# Chanel.net
KiCad netlist of a schematic drawn in Altium Designer
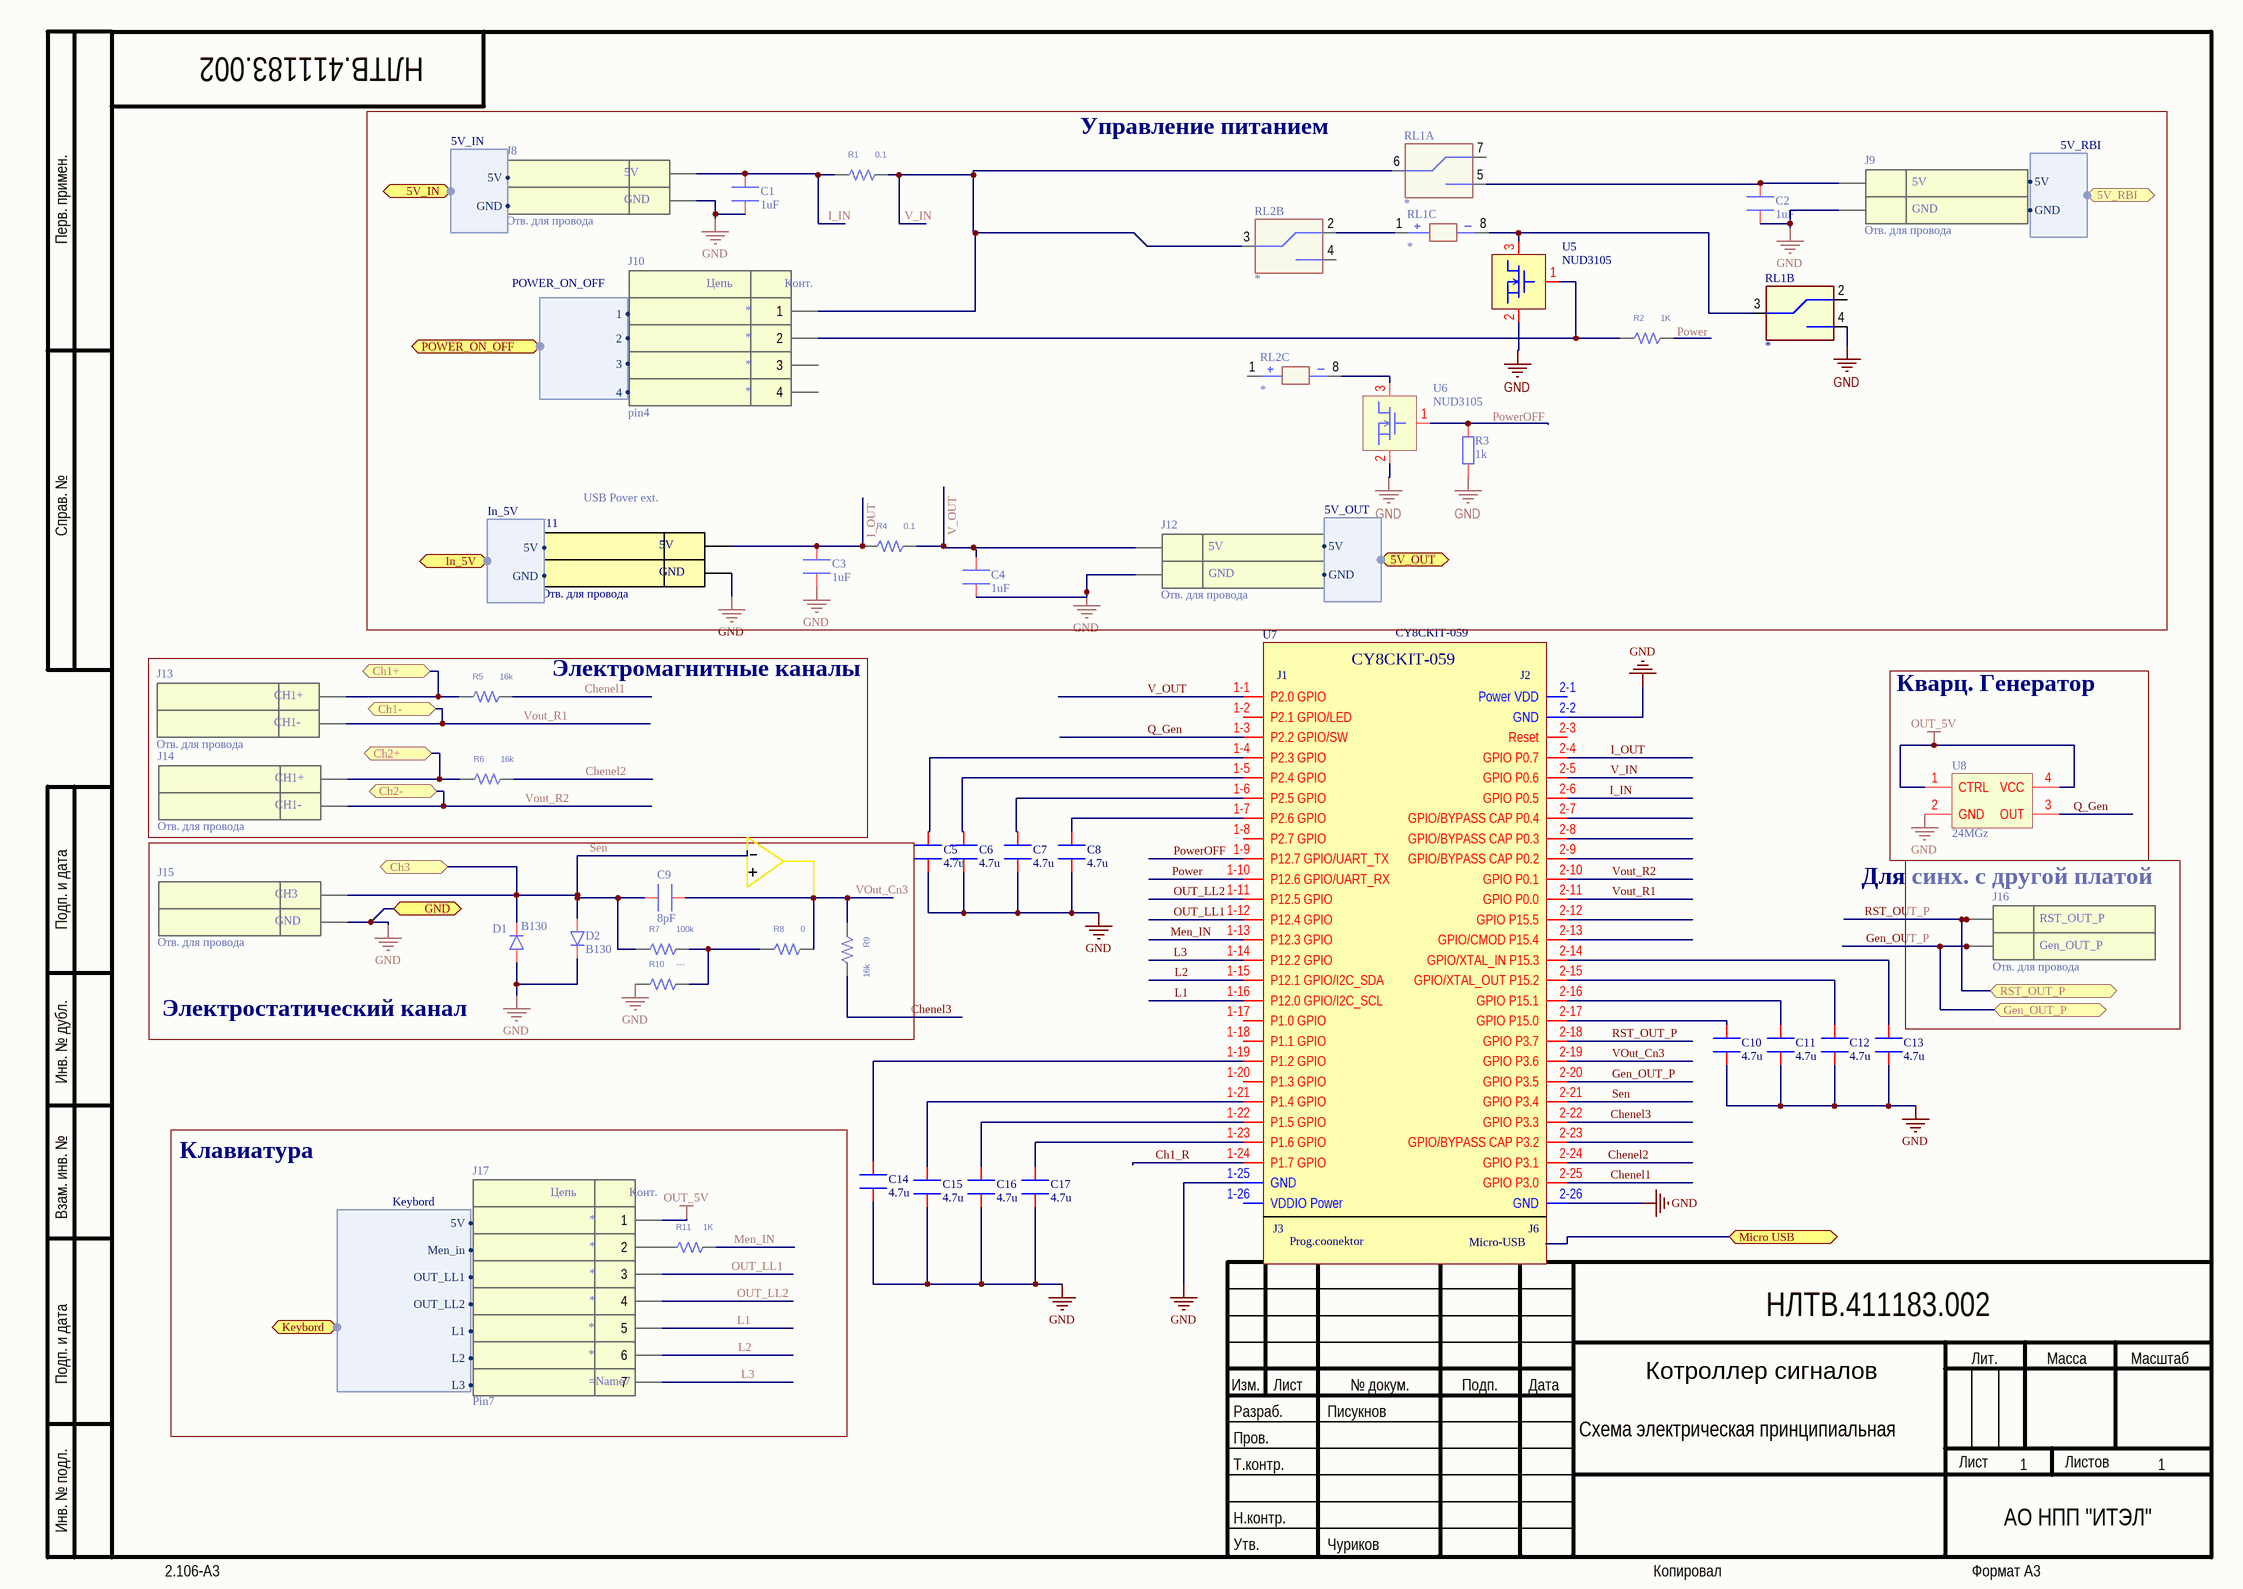
[diagram p0: Chanel.SchDoc]

(export (version "E")
  (design (tool "Eeschema 10.0.6"))
  (components
    (comp (ref "C1") (value "1uF") (footprint "SMD0603") (libsource (lib "Lib_001") (part "CAP")))
    (comp (ref "C2") (value "1uF") (footprint "SMD0603") (libsource (lib "Lib_001") (part "CAP")))
    (comp (ref "C3") (value "1uF") (footprint "SMD0603") (libsource (lib "Lib_001") (part "CAP")))
    (comp (ref "C4") (value "1uF") (footprint "SMD0603") (libsource (lib "Lib_001") (part "CAP")))
    (comp (ref "C5") (value "4.7u") (footprint "SMD0805") (libsource (lib "Lib_001") (part "CAP")))
    (comp (ref "C6") (value "4.7u") (footprint "SMD0805") (libsource (lib "Lib_001") (part "CAP")))
    (comp (ref "C7") (value "4.7u") (footprint "SMD0805") (libsource (lib "Lib_001") (part "CAP")))
    (comp (ref "C8") (value "4.7u") (footprint "SMD0805") (libsource (lib "Lib_001") (part "CAP")))
    (comp (ref "C9") (value "8pF") (footprint "SMD0805") (libsource (lib "Lib_001") (part "CAP")))
    (comp (ref "C10") (value "4.7u") (footprint "SMD0805") (libsource (lib "Lib_001") (part "CAP")))
    (comp (ref "C11") (value "4.7u") (footprint "SMD0805") (libsource (lib "Lib_001") (part "CAP")))
    (comp (ref "C12") (value "4.7u") (footprint "SMD0805") (libsource (lib "Lib_001") (part "CAP")))
    (comp (ref "C13") (value "4.7u") (footprint "SMD0805") (libsource (lib "Lib_001") (part "CAP")))
    (comp (ref "C14") (value "4.7u") (footprint "SMD0805") (libsource (lib "Lib_001") (part "CAP")))
    (comp (ref "C15") (value "4.7u") (footprint "SMD0805") (libsource (lib "Lib_001") (part "CAP")))
    (comp (ref "C16") (value "4.7u") (footprint "SMD0805") (libsource (lib "Lib_001") (part "CAP")))
    (comp (ref "C17") (value "4.7u") (footprint "SMD0805") (libsource (lib "Lib_001") (part "CAP")))
    (comp (ref "D1") (value "B130") (footprint "SMA DIOD") (libsource (lib "Lib_001") (part "DIOD")))
    (comp (ref "D2") (value "B130") (footprint "SMA DIOD") (libsource (lib "Lib_001") (part "DIOD")))
    (comp (ref "J8")
      (value "Отв. для провода")
      (footprint "JAMPER 2")
      (libsource (lib "") (part "pin2_continuation_1"))
    )
    (comp (ref "J9")
      (value "Отв. для провода")
      (footprint "JAMPER 2")
      (libsource (lib "Lib_001") (part "pin2_continuation"))
    )
    (comp (ref "J10") (value "pin4") (footprint "MF-4MA") (libsource (lib "Lib_001") (part "pin4")))
    (comp (ref "J11")
      (value "Отв. для провода")
      (footprint "JAMPER 2")
      (libsource (lib "") (part "pin2_continuation_1"))
    )
    (comp (ref "J12")
      (value "Отв. для провода")
      (footprint "JAMPER 2")
      (libsource (lib "Lib_001") (part "pin2_continuation"))
    )
    (comp (ref "J13")
      (value "Отв. для провода")
      (footprint "JAMPER 2")
      (libsource (lib "") (part "pin2_continuation_1"))
    )
    (comp (ref "J14")
      (value "Отв. для провода")
      (footprint "JAMPER 2")
      (libsource (lib "") (part "pin2_continuation_1"))
    )
    (comp (ref "J15")
      (value "Отв. для провода")
      (footprint "JAMPER 2")
      (libsource (lib "") (part "pin2_continuation_1"))
    )
    (comp (ref "J16")
      (value "Отв. для провода")
      (footprint "JAMPER 2")
      (libsource (lib "Lib_001") (part "pin2_continuation"))
    )
    (comp (ref "J17") (value "Pin7") (footprint "ECH350V-06P") (libsource (lib "Lib_001") (part "Pin7")))
    (comp (ref "R1")
      (value "0.1")
      (footprint "SMD1206")
      (fields (field (name "POWER") "RMAX") (field (name "VOLTAGE") "RVMAX"))
      (libsource (lib "*") (part "R"))
    )
    (comp (ref "R2")
      (value "1K")
      (footprint "SMD1206")
      (fields (field (name "POWER") "RMAX") (field (name "VOLTAGE") "RVMAX"))
      (libsource (lib "*") (part "R"))
    )
    (comp (ref "R3") (value "1k") (footprint "SMD0805") (libsource (lib "Lib_001") (part "RES_SMD")))
    (comp (ref "R4")
      (value "0.1")
      (footprint "SMD1206")
      (fields (field (name "POWER") "RMAX") (field (name "VOLTAGE") "RVMAX"))
      (libsource (lib "*") (part "R"))
    )
    (comp (ref "R5")
      (value "16k")
      (footprint "SMD1206")
      (fields (field (name "POWER") "RMAX") (field (name "VOLTAGE") "RVMAX"))
      (libsource (lib "*") (part "R"))
    )
    (comp (ref "R6")
      (value "16k")
      (footprint "SMD1206")
      (fields (field (name "POWER") "RMAX") (field (name "VOLTAGE") "RVMAX"))
      (libsource (lib "*") (part "R"))
    )
    (comp (ref "R7")
      (value "100k")
      (footprint "SMD1206")
      (fields (field (name "POWER") "RMAX") (field (name "VOLTAGE") "RVMAX"))
      (libsource (lib "*") (part "R"))
    )
    (comp (ref "R8")
      (value "0")
      (footprint "SMD1206")
      (fields (field (name "POWER") "RMAX") (field (name "VOLTAGE") "RVMAX"))
      (libsource (lib "*") (part "R"))
    )
    (comp (ref "R9")
      (value "16k")
      (footprint "SMD1206")
      (fields (field (name "POWER") "RMAX") (field (name "VOLTAGE") "RVMAX"))
      (libsource (lib "*") (part "R"))
    )
    (comp (ref "R10")
      (value "---")
      (footprint "SMD1206")
      (fields (field (name "POWER") "RMAX") (field (name "VOLTAGE") "RVMAX"))
      (libsource (lib "*") (part "R"))
    )
    (comp (ref "R11")
      (value "1K")
      (footprint "SMD1206")
      (fields (field (name "POWER") "RMAX") (field (name "VOLTAGE") "RVMAX"))
      (libsource (lib "*") (part "R"))
    )
    (comp (ref "RL1") (value "*") (footprint "IM06GR") (libsource (lib "Lib_001") (part "Relay_2 switch")))
    (comp (ref "RL2") (value "*") (footprint "IM06GR") (libsource (lib "Lib_001") (part "Relay_2 switch")))
    (comp (ref "U5") (value "NUD3105") (footprint "SOT-23") (libsource (lib "Lib_001") (part "NUD3105")))
    (comp (ref "U6") (value "NUD3105") (footprint "SOT-23") (libsource (lib "Lib_001") (part "NUD3105")))
    (comp (ref "U7")
      (value "CY8CKIT-059")
      (footprint "CY8CKIT-059")
      (libsource (lib "Lib_001") (part "CY8CKIT-059"))
    )
    (comp (ref "U8") (value "24MGz") (libsource (lib "Lib_001") (part "KXO-97")))
  )
  (nets
    (net (code "7") (name "/Ch1+") (class "Default")
      (node (ref "J13") (pin "1") (pinfunction "1_1") (pintype "passive"))
      (node (ref "R5") (pin "1") (pinfunction "1_1") (pintype "passive"))
    )
    (net (code "8") (name "/Ch1_R") (class "Default")
      (node (ref "U7") (pin "1-24") (pinfunction "P1.7_GPIO_1-24") (pintype "passive"))
    )
    (net (code "9") (name "/Ch2+") (class "Default")
      (node (ref "J14") (pin "1") (pinfunction "1_1") (pintype "passive"))
      (node (ref "R6") (pin "1") (pinfunction "1_1") (pintype "passive"))
    )
    (net (code "10") (name "/Chenel1") (class "Default")
      (node (ref "R5") (pin "2") (pinfunction "2_2") (pintype "passive"))
      (node (ref "U7") (pin "2-25") (pinfunction "GPIO_P3.0_2-25") (pintype "passive"))
    )
    (net (code "11") (name "/Chenel2") (class "Default")
      (node (ref "R6") (pin "2") (pinfunction "2_2") (pintype "passive"))
      (node (ref "U7") (pin "2-24") (pinfunction "GPIO_P3.1_2-24") (pintype "passive"))
    )
    (net (code "12") (name "/Chenel3") (class "Default")
      (node (ref "R9") (pin "2") (pinfunction "2_2") (pintype "passive"))
      (node (ref "U7") (pin "2-22") (pinfunction "GPIO_P3.3_2-22") (pintype "passive"))
    )
    (net (code "13") (name "/Gen_OUT_P") (class "Default")
      (node (ref "J16") (pin "2") (pinfunction "2_2") (pintype "passive"))
      (node (ref "U7") (pin "2-20") (pinfunction "GPIO_P3.5_2-20") (pintype "passive"))
    )
    (net (code "14") (name "/I_IN") (class "Default")
      (node (ref "C1") (pin "2") (pinfunction "2_2") (pintype "passive"))
      (node (ref "J8") (pin "1") (pinfunction "1_1") (pintype "passive"))
      (node (ref "R1") (pin "1") (pinfunction "1_1") (pintype "passive"))
      (node (ref "U7") (pin "2-6") (pinfunction "GPIO_P0.5_2-6") (pintype "passive"))
    )
    (net (code "15") (name "/I_OUT") (class "Default")
      (node (ref "C3") (pin "2") (pinfunction "2_2") (pintype "passive"))
      (node (ref "J11") (pin "1") (pinfunction "1_1") (pintype "passive"))
      (node (ref "R4") (pin "1") (pinfunction "1_1") (pintype "passive"))
      (node (ref "U7") (pin "2-4") (pinfunction "GPIO_P0.7_2-4") (pintype "passive"))
    )
    (net (code "16") (name "/L1") (class "Default")
      (node (ref "J17") (pin "5") (pinfunction "5_5") (pintype "passive"))
      (node (ref "U7") (pin "1-16") (pinfunction "P12.0_GPIO/I2C_SCL_1-16") (pintype "passive"))
    )
    (net (code "17") (name "/L2") (class "Default")
      (node (ref "J17") (pin "6") (pinfunction "6_6") (pintype "passive"))
      (node (ref "U7") (pin "1-15") (pinfunction "P12.1_GPIO/I2C_SDA_1-15") (pintype "passive"))
    )
    (net (code "18") (name "/L3") (class "Default")
      (node (ref "J17") (pin "7") (pinfunction "7_7") (pintype "passive"))
      (node (ref "U7") (pin "1-14") (pinfunction "P12.2_GPIO_1-14") (pintype "passive"))
    )
    (net (code "19") (name "/Men_IN") (class "Default")
      (node (ref "R11") (pin "2") (pinfunction "2_2") (pintype "passive"))
      (node (ref "U7") (pin "1-13") (pinfunction "P12.3_GPIO_1-13") (pintype "passive"))
    )
    (net (code "21") (name "/OUT_LL1") (class "Default")
      (node (ref "J17") (pin "3") (pinfunction "3_3") (pintype "passive"))
      (node (ref "U7") (pin "1-12") (pinfunction "P12.4_GPIO_1-12") (pintype "passive"))
    )
    (net (code "22") (name "/OUT_LL2") (class "Default")
      (node (ref "J17") (pin "4") (pinfunction "4_4") (pintype "passive"))
      (node (ref "U7") (pin "1-11") (pinfunction "P12.5_GPIO_1-11") (pintype "passive"))
    )
    (net (code "23") (name "/Power") (class "Default")
      (node (ref "U7") (pin "1-10") (pinfunction "P12.6_GPIO/UART_RX_1-10") (pintype "passive"))
    )
    (net (code "24") (name "/PowerOFF") (class "Default")
      (node (ref "U7") (pin "1-9") (pinfunction "P12.7_GPIO/UART_TX_1-9") (pintype "passive"))
    )
    (net (code "25") (name "/Q_Gen") (class "Default")
      (node (ref "U7") (pin "1-3") (pinfunction "P2.2_GPIO/SW_1-3") (pintype "passive"))
      (node (ref "U8") (pin "3") (pinfunction "OUT_3") (pintype "passive"))
    )
    (net (code "26") (name "/RST_OUT_P") (class "Default")
      (node (ref "J16") (pin "1") (pinfunction "1_1") (pintype "passive"))
      (node (ref "U7") (pin "2-18") (pinfunction "GPIO_P3.7_2-18") (pintype "passive"))
    )
    (net (code "27") (name "/Sen") (class "Default")
      (node (ref "C9") (pin "2") (pinfunction "2_2") (pintype "passive"))
      (node (ref "D1") (pin "K") (pinfunction "K_K") (pintype "passive"))
      (node (ref "D2") (pin "A") (pinfunction "A_A") (pintype "passive"))
      (node (ref "J15") (pin "1") (pinfunction "1_1") (pintype "passive"))
      (node (ref "R7") (pin "1") (pinfunction "1_1") (pintype "passive"))
      (node (ref "U7") (pin "2-21") (pinfunction "GPIO_P3.4_2-21") (pintype "passive"))
    )
    (net (code "28") (name "/VOut_Cn3") (class "Default")
      (node (ref "C9") (pin "1") (pinfunction "1_1") (pintype "passive"))
      (node (ref "R8") (pin "2") (pinfunction "2_2") (pintype "passive"))
      (node (ref "R9") (pin "1") (pinfunction "1_1") (pintype "passive"))
      (node (ref "U7") (pin "2-19") (pinfunction "GPIO_P3.6_2-19") (pintype "passive"))
    )
    (net (code "29") (name "/V_IN") (class "Default")
      (node (ref "J10") (pin "1") (pinfunction "1_1") (pintype "passive"))
      (node (ref "R1") (pin "2") (pinfunction "2_2") (pintype "passive"))
      (node (ref "RL1") (pin "6") (pinfunction "A9_6") (pintype "passive"))
      (node (ref "RL2") (pin "3") (pinfunction "A12_3") (pintype "passive"))
      (node (ref "U7") (pin "2-5") (pinfunction "GPIO_P0.6_2-5") (pintype "passive"))
    )
    (net (code "30") (name "/V_OUT") (class "Default")
      (node (ref "C4") (pin "2") (pinfunction "2_2") (pintype "passive"))
      (node (ref "J12") (pin "1") (pinfunction "1_1") (pintype "passive"))
      (node (ref "R4") (pin "2") (pinfunction "2_2") (pintype "passive"))
      (node (ref "U7") (pin "1-1") (pinfunction "P2.0_GPIO_1-1") (pintype "passive"))
    )
    (net (code "31") (name "/Vout_R1") (class "Default")
      (node (ref "J13") (pin "2") (pinfunction "2_2") (pintype "passive"))
      (node (ref "U7") (pin "2-11") (pinfunction "GPIO_P0.0_2-11") (pintype "passive"))
    )
    (net (code "32") (name "/Vout_R2") (class "Default")
      (node (ref "J14") (pin "2") (pinfunction "2_2") (pintype "passive"))
      (node (ref "U7") (pin "2-10") (pinfunction "GPIO_P0.1_2-10") (pintype "passive"))
    )
    (net (code "39") (name "GND") (class "Default")
      (node (ref "C1") (pin "1") (pinfunction "1_1") (pintype "passive"))
      (node (ref "C10") (pin "1") (pinfunction "1_1") (pintype "passive"))
      (node (ref "C11") (pin "1") (pinfunction "1_1") (pintype "passive"))
      (node (ref "C12") (pin "1") (pinfunction "1_1") (pintype "passive"))
      (node (ref "C13") (pin "1") (pinfunction "1_1") (pintype "passive"))
      (node (ref "C14") (pin "1") (pinfunction "1_1") (pintype "passive"))
      (node (ref "C15") (pin "1") (pinfunction "1_1") (pintype "passive"))
      (node (ref "C16") (pin "1") (pinfunction "1_1") (pintype "passive"))
      (node (ref "C17") (pin "1") (pinfunction "1_1") (pintype "passive"))
      (node (ref "C2") (pin "1") (pinfunction "1_1") (pintype "passive"))
      (node (ref "C3") (pin "1") (pinfunction "1_1") (pintype "passive"))
      (node (ref "C4") (pin "1") (pinfunction "1_1") (pintype "passive"))
      (node (ref "C5") (pin "1") (pinfunction "1_1") (pintype "passive"))
      (node (ref "C6") (pin "1") (pinfunction "1_1") (pintype "passive"))
      (node (ref "C7") (pin "1") (pinfunction "1_1") (pintype "passive"))
      (node (ref "C8") (pin "1") (pinfunction "1_1") (pintype "passive"))
      (node (ref "D1") (pin "A") (pinfunction "A_A") (pintype "passive"))
      (node (ref "D2") (pin "K") (pinfunction "K_K") (pintype "passive"))
      (node (ref "J11") (pin "2") (pinfunction "2_2") (pintype "passive"))
      (node (ref "J12") (pin "2") (pinfunction "2_2") (pintype "passive"))
      (node (ref "J15") (pin "2") (pinfunction "2_2") (pintype "passive"))
      (node (ref "J8") (pin "2") (pinfunction "2_2") (pintype "passive"))
      (node (ref "J9") (pin "2") (pinfunction "2_2") (pintype "passive"))
      (node (ref "R10") (pin "1") (pinfunction "1_1") (pintype "passive"))
      (node (ref "R3") (pin "1") (pinfunction "1_1") (pintype "passive"))
      (node (ref "RL1") (pin "4") (pinfunction "A14_4") (pintype "passive"))
      (node (ref "U5") (pin "2") (pinfunction "S_2") (pintype "passive"))
      (node (ref "U6") (pin "2") (pinfunction "S_2") (pintype "passive"))
      (node (ref "U7") (pin "1-25") (pinfunction "GND_1-25") (pintype "passive"))
      (node (ref "U7") (pin "2-2") (pinfunction "GND_2-2") (pintype "passive"))
      (node (ref "U7") (pin "2-26") (pinfunction "GND_2-26") (pintype "passive"))
      (node (ref "U8") (pin "2") (pinfunction "GND_2") (pintype "passive"))
    )
    (net (code "40") (name "Net-(J17-Pad2)") (class "Default")
      (node (ref "J17") (pin "2") (pinfunction "2_2") (pintype "passive"))
      (node (ref "R11") (pin "1") (pinfunction "1_1") (pintype "passive"))
    )
    (net (code "41") (name "Net-(R10-Pad2)") (class "Default")
      (node (ref "R10") (pin "2") (pinfunction "2_2") (pintype "passive"))
      (node (ref "R7") (pin "2") (pinfunction "2_2") (pintype "passive"))
      (node (ref "R8") (pin "1") (pinfunction "1_1") (pintype "passive"))
    )
    (net (code "42") (name "Net-(RL1A-A11)") (class "Default")
      (node (ref "C2") (pin "2") (pinfunction "2_2") (pintype "passive"))
      (node (ref "J9") (pin "1") (pinfunction "1_1") (pintype "passive"))
      (node (ref "RL1") (pin "5") (pinfunction "A11_5") (pintype "passive"))
    )
    (net (code "43") (name "Net-(RL1B-A12)") (class "Default")
      (node (ref "RL1") (pin "3") (pinfunction "A12_3") (pintype "passive"))
      (node (ref "RL1") (pin "8") (pinfunction "-_8") (pintype "passive"))
      (node (ref "U5") (pin "3") (pinfunction "D_3") (pintype "passive"))
    )
    (net (code "44") (name "Net-(RL1C-+)") (class "Default")
      (node (ref "RL1") (pin "1") (pinfunction "+_1") (pintype "passive"))
      (node (ref "RL2") (pin "2") (pinfunction "A13_2") (pintype "passive"))
    )
    (net (code "45") (name "Net-(RL2C--)") (class "Default")
      (node (ref "RL2") (pin "8") (pinfunction "-_8") (pintype "passive"))
      (node (ref "U6") (pin "3") (pinfunction "D_3") (pintype "passive"))
    )
    (net (code "46") (name "Net-(U5-G)") (class "Default")
      (node (ref "J10") (pin "2") (pinfunction "2_2") (pintype "passive"))
      (node (ref "R2") (pin "1") (pinfunction "1_1") (pintype "passive"))
      (node (ref "U5") (pin "1") (pinfunction "G_1") (pintype "passive"))
    )
    (net (code "47") (name "Net-(U6-G)") (class "Default")
      (node (ref "R3") (pin "2") (pinfunction "2_2") (pintype "passive"))
      (node (ref "U6") (pin "1") (pinfunction "G_1") (pintype "passive"))
    )
    (net (code "48") (name "Net-(U7-GPIO_P15.0)") (class "Default")
      (node (ref "C10") (pin "2") (pinfunction "2_2") (pintype "passive"))
      (node (ref "U7") (pin "2-17") (pinfunction "GPIO_P15.0_2-17") (pintype "passive"))
    )
    (net (code "49") (name "Net-(U7-GPIO_P15.1)") (class "Default")
      (node (ref "C11") (pin "2") (pinfunction "2_2") (pintype "passive"))
      (node (ref "U7") (pin "2-16") (pinfunction "GPIO_P15.1_2-16") (pintype "passive"))
    )
    (net (code "50") (name "Net-(U7-GPIO{slash}XTAL_IN_P15.3)") (class "Default")
      (node (ref "C13") (pin "2") (pinfunction "2_2") (pintype "passive"))
      (node (ref "U7") (pin "2-14") (pinfunction "GPIO/XTAL_IN_P15.3_2-14") (pintype "passive"))
    )
    (net (code "51") (name "Net-(U7-GPIO{slash}XTAL_OUT_P15.2)") (class "Default")
      (node (ref "C12") (pin "2") (pinfunction "2_2") (pintype "passive"))
      (node (ref "U7") (pin "2-15") (pinfunction "GPIO/XTAL_OUT_P15.2_2-15") (pintype "passive"))
    )
    (net (code "52") (name "Net-(U7-P1.2_GPIO)") (class "Default")
      (node (ref "C14") (pin "2") (pinfunction "2_2") (pintype "passive"))
      (node (ref "U7") (pin "1-19") (pinfunction "P1.2_GPIO_1-19") (pintype "passive"))
    )
    (net (code "53") (name "Net-(U7-P1.4_GPIO)") (class "Default")
      (node (ref "C15") (pin "2") (pinfunction "2_2") (pintype "passive"))
      (node (ref "U7") (pin "1-21") (pinfunction "P1.4_GPIO_1-21") (pintype "passive"))
    )
    (net (code "54") (name "Net-(U7-P1.5_GPIO)") (class "Default")
      (node (ref "C16") (pin "2") (pinfunction "2_2") (pintype "passive"))
      (node (ref "U7") (pin "1-22") (pinfunction "P1.5_GPIO_1-22") (pintype "passive"))
    )
    (net (code "55") (name "Net-(U7-P1.6_GPIO)") (class "Default")
      (node (ref "C17") (pin "2") (pinfunction "2_2") (pintype "passive"))
      (node (ref "U7") (pin "1-23") (pinfunction "P1.6_GPIO_1-23") (pintype "passive"))
    )
    (net (code "56") (name "Net-(U7-P2.3_GPIO)") (class "Default")
      (node (ref "C5") (pin "2") (pinfunction "2_2") (pintype "passive"))
      (node (ref "U7") (pin "1-4") (pinfunction "P2.3_GPIO_1-4") (pintype "passive"))
    )
    (net (code "57") (name "Net-(U7-P2.4_GPIO)") (class "Default")
      (node (ref "C6") (pin "2") (pinfunction "2_2") (pintype "passive"))
      (node (ref "U7") (pin "1-5") (pinfunction "P2.4_GPIO_1-5") (pintype "passive"))
    )
    (net (code "58") (name "Net-(U7-P2.5_GPIO)") (class "Default")
      (node (ref "C7") (pin "2") (pinfunction "2_2") (pintype "passive"))
      (node (ref "U7") (pin "1-6") (pinfunction "P2.5_GPIO_1-6") (pintype "passive"))
    )
    (net (code "59") (name "Net-(U7-P2.6_GPIO)") (class "Default")
      (node (ref "C8") (pin "2") (pinfunction "2_2") (pintype "passive"))
      (node (ref "U7") (pin "1-7") (pinfunction "P2.6_GPIO_1-7") (pintype "passive"))
    )
    (net (code "60") (name "OUT_5V") (class "Default")
      (node (ref "J17") (pin "1") (pinfunction "1_1") (pintype "passive"))
      (node (ref "U8") (pin "1") (pinfunction "CTRL_1") (pintype "passive"))
      (node (ref "U8") (pin "4") (pinfunction "VCC_4") (pintype "passive"))
    )
    (net (code "61") (name "unconnected-(J10-Pad3)") (class "Default")
      (node (ref "J10") (pin "3") (pinfunction "3_3") (pintype "passive"))
    )
    (net (code "62") (name "unconnected-(J10-Pad4)") (class "Default")
      (node (ref "J10") (pin "4") (pinfunction "4_4") (pintype "passive"))
    )
    (net (code "63") (name "unconnected-(R2-Pad2)") (class "Default")
      (node (ref "R2") (pin "2") (pinfunction "2_2") (pintype "passive"))
    )
    (net (code "64") (name "unconnected-(RL1A-A10-Pad7)") (class "Default")
      (node (ref "RL1") (pin "7") (pinfunction "A10_7") (pintype "passive"))
    )
    (net (code "65") (name "unconnected-(RL1B-A13-Pad2)") (class "Default")
      (node (ref "RL1") (pin "2") (pinfunction "A13_2") (pintype "passive"))
    )
    (net (code "66") (name "unconnected-(RL2B-A14-Pad4)") (class "Default")
      (node (ref "RL2") (pin "4") (pinfunction "A14_4") (pintype "passive"))
    )
    (net (code "67") (name "unconnected-(RL2C-+-Pad1)") (class "Default")
      (node (ref "RL2") (pin "1") (pinfunction "+_1") (pintype "passive"))
    )
    (net (code "68") (name "unconnected-(U7-GPIO_P15.5-Pad2-12)") (class "Default")
      (node (ref "U7") (pin "2-12") (pinfunction "GPIO_P15.5_2-12") (pintype "passive"))
    )
    (net (code "69") (name "unconnected-(U7-GPIO{slash}BYPASS_CAP_P0.2-Pad2-9)") (class "Default")
      (node (ref "U7") (pin "2-9") (pinfunction "GPIO/BYPASS_CAP_P0.2_2-9") (pintype "passive"))
    )
    (net (code "70") (name "unconnected-(U7-GPIO{slash}BYPASS_CAP_P0.3-Pad2-8)") (class "Default")
      (node (ref "U7") (pin "2-8") (pinfunction "GPIO/BYPASS_CAP_P0.3_2-8") (pintype "passive"))
    )
    (net (code "71") (name "unconnected-(U7-GPIO{slash}BYPASS_CAP_P0.4-Pad2-7)") (class "Default")
      (node (ref "U7") (pin "2-7") (pinfunction "GPIO/BYPASS_CAP_P0.4_2-7") (pintype "passive"))
    )
    (net (code "72") (name "unconnected-(U7-GPIO{slash}BYPASS_CAP_P3.2-Pad2-23)") (class "Default")
      (node (ref "U7") (pin "2-23") (pinfunction "GPIO/BYPASS_CAP_P3.2_2-23") (pintype "passive"))
    )
    (net (code "73") (name "unconnected-(U7-GPIO{slash}CMOD_P15.4-Pad2-13)") (class "Default")
      (node (ref "U7") (pin "2-13") (pinfunction "GPIO/CMOD_P15.4_2-13") (pintype "passive"))
    )
    (net (code "74") (name "unconnected-(U7-P1.0_GPIO-Pad1-17)") (class "Default")
      (node (ref "U7") (pin "1-17") (pinfunction "P1.0_GPIO_1-17") (pintype "passive"))
    )
    (net (code "75") (name "unconnected-(U7-P1.1_GPIO-Pad1-18)") (class "Default")
      (node (ref "U7") (pin "1-18") (pinfunction "P1.1_GPIO_1-18") (pintype "passive"))
    )
    (net (code "76") (name "unconnected-(U7-P1.3_GPIO-Pad1-20)") (class "Default")
      (node (ref "U7") (pin "1-20") (pinfunction "P1.3_GPIO_1-20") (pintype "passive"))
    )
    (net (code "77") (name "unconnected-(U7-P2.1_GPIO{slash}LED-Pad1-2)") (class "Default")
      (node (ref "U7") (pin "1-2") (pinfunction "P2.1_GPIO/LED_1-2") (pintype "passive"))
    )
    (net (code "78") (name "unconnected-(U7-P2.7_GPIO-Pad1-8)") (class "Default")
      (node (ref "U7") (pin "1-8") (pinfunction "P2.7_GPIO_1-8") (pintype "passive"))
    )
    (net (code "79") (name "unconnected-(U7-Power_VDD-Pad2-1)") (class "Default")
      (node (ref "U7") (pin "2-1") (pinfunction "Power_VDD_2-1") (pintype "passive"))
    )
    (net (code "80") (name "unconnected-(U7-Reset-Pad2-3)") (class "Default")
      (node (ref "U7") (pin "2-3") (pinfunction "Reset_2-3") (pintype "passive"))
    )
    (net (code "81") (name "unconnected-(U7-VDDIO_Power-Pad1-26)") (class "Default")
      (node (ref "U7") (pin "1-26") (pinfunction "VDDIO_Power_1-26") (pintype "passive"))
    )
  )
)
